# CAN.net
KiCad netlist of a schematic drawn in Altium Designer
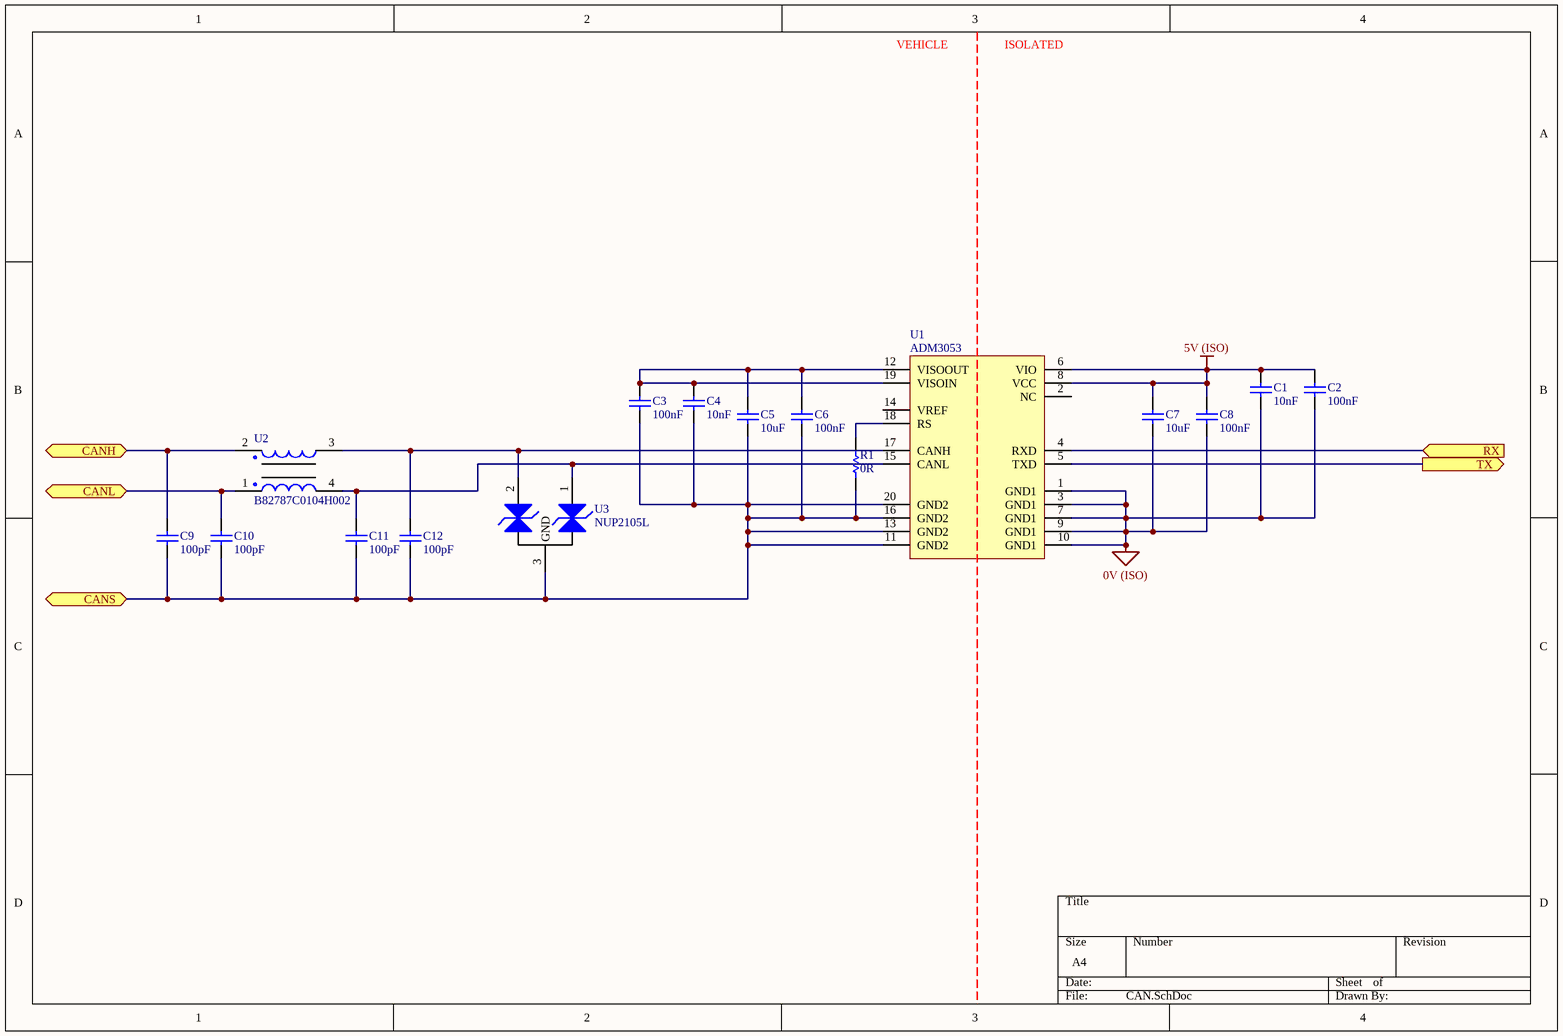
[diagram p0: CAN.SchDoc]

(export (version "E")
  (design (tool "Eeschema 10.0.6"))
  (components
    (comp (ref "C1")
      (value "10nF")
      (footprint "1206")
      (fields
        (field (name "PART NUMBER") "GCM3195C2A103JA16D")
        (field (name "TOLERANCE") "5%")
        (field (name "MANUFACTURER") "muRata")
      )
      (libsource (lib "ts_19-standard-library") (part "Capacitor"))
    )
    (comp (ref "C2")
      (value "100nF")
      (footprint "0805")
      (fields
        (field (name "PART NUMBER") "GCM21BR71E104KA37L")
        (field (name "TOLERANCE") "10%")
        (field (name "MANUFACTURER") "muRata")
      )
      (libsource (lib "ts_19-standard-library") (part "Capacitor"))
    )
    (comp (ref "C3")
      (value "100nF")
      (footprint "0805")
      (fields
        (field (name "PART NUMBER") "GCM21BR71E104KA37L")
        (field (name "TOLERANCE") "10%")
        (field (name "MANUFACTURER") "muRata")
      )
      (libsource (lib "ts_19-standard-library") (part "Capacitor"))
    )
    (comp (ref "C4")
      (value "10nF")
      (footprint "1206")
      (fields
        (field (name "PART NUMBER") "GCM3195C2A103JA16D")
        (field (name "TOLERANCE") "5%")
        (field (name "MANUFACTURER") "muRata")
      )
      (libsource (lib "ts_19-standard-library") (part "Capacitor"))
    )
    (comp (ref "C5")
      (value "10uF")
      (footprint "0805")
      (fields
        (field (name "PART NUMBER") "GRM21BR6YA106KE43L")
        (field (name "TOLERANCE") "10%")
        (field (name "MANUFACTURER") "muRata")
      )
      (libsource (lib "ts_19-standard-library") (part "Capacitor"))
    )
    (comp (ref "C6")
      (value "100nF")
      (footprint "0805")
      (fields
        (field (name "PART NUMBER") "GCM21BR71E104KA37L")
        (field (name "TOLERANCE") "10%")
        (field (name "MANUFACTURER") "muRata")
      )
      (libsource (lib "ts_19-standard-library") (part "Capacitor"))
    )
    (comp (ref "C7")
      (value "10uF")
      (footprint "0805")
      (fields
        (field (name "PART NUMBER") "GRM21BR6YA106KE43L")
        (field (name "TOLERANCE") "10%")
        (field (name "MANUFACTURER") "muRata")
      )
      (libsource (lib "ts_19-standard-library") (part "Capacitor"))
    )
    (comp (ref "C8")
      (value "100nF")
      (footprint "0805")
      (fields
        (field (name "PART NUMBER") "GCM21BR71E104KA37L")
        (field (name "TOLERANCE") "10%")
        (field (name "MANUFACTURER") "muRata")
      )
      (libsource (lib "ts_19-standard-library") (part "Capacitor"))
    )
    (comp (ref "C9")
      (value "100pF")
      (footprint "0805")
      (fields
        (field (name "PART NUMBER") "GCM21B5C1H101JA37L")
        (field (name "TOLERANCE") "5%")
        (field (name "MANUFACTURER") "muRata")
      )
      (libsource (lib "ts_19-standard-library") (part "Capacitor"))
    )
    (comp (ref "C10")
      (value "100pF")
      (footprint "0805")
      (fields
        (field (name "PART NUMBER") "GCM21B5C1H101JA37L")
        (field (name "TOLERANCE") "5%")
        (field (name "MANUFACTURER") "muRata")
      )
      (libsource (lib "ts_19-standard-library") (part "Capacitor"))
    )
    (comp (ref "C11")
      (value "100pF")
      (footprint "0805")
      (fields
        (field (name "PART NUMBER") "GCM21B5C1H101JA37L")
        (field (name "TOLERANCE") "5%")
        (field (name "MANUFACTURER") "muRata")
      )
      (libsource (lib "ts_19-standard-library") (part "Capacitor"))
    )
    (comp (ref "C12")
      (value "100pF")
      (footprint "0805")
      (fields
        (field (name "PART NUMBER") "GCM21B5C1H101JA37L")
        (field (name "TOLERANCE") "5%")
        (field (name "MANUFACTURER") "muRata")
      )
      (libsource (lib "ts_19-standard-library") (part "Capacitor"))
    )
    (comp (ref "R1")
      (value "0R")
      (footprint "0805")
      (fields
        (field (name "TOLERANCE") "0.01")
        (field (name "PART NUMBER") "RC0805FR070RL")
        (field (name "MANUFACTURER") "YAGEO")
      )
      (libsource (lib "ts_19-standard-library") (part "Resistor"))
    )
    (comp (ref "U1")
      (value "ADM3053")
      (footprint "AD SOIC-W 20")
      (description "Isolated CAN Transceiver")
      (fields
        (field (name "MANUFACTURER") "Analogue Devices")
        (field (name "DIGIKEY PART NUMBER") "ADM3053BRWZ-ND")
      )
      (libsource (lib "ts_19-standard-library") (part "ADM3053"))
    )
    (comp (ref "U2")
      (value "B82787C0104H002")
      (footprint "TDK 4-PC Pad")
      (description "Common mode choke intended for CANBUS 150mA 50V)")
      (fields
        (field (name "MANUFACTURER") "EPCOS (TDK)")
        (field (name "DIGIKEY PART NUMBER") "495-4598-2-ND")
      )
      (libsource (lib "ts_19-standard-library") (part "B82787C0104H002"))
    )
    (comp (ref "U3")
      (value "NUP2105L")
      (footprint "ON SOT-23")
      (description "Dual Line CAN Bus Protector")
      (fields
        (field (name "MANUFACTURER") "ON Semiconductor")
        (field (name "DIGIKEY PART NUMBER") "NUP2105LT1GOSCT-ND")
      )
      (libsource (lib "ts_19-standard-library") (part "NUP2105L"))
    )
  )
  (nets
    (net (code "1") (name "/CANH") (class "Default")
      (node (ref "C9") (pin "2") (pinfunction "2_2") (pintype "passive"))
      (node (ref "U2") (pin "2") (pinfunction "2_2") (pintype "passive"))
    )
    (net (code "2") (name "/CANL") (class "Default")
      (node (ref "C10") (pin "2") (pinfunction "2_2") (pintype "passive"))
      (node (ref "U2") (pin "1") (pinfunction "1_1") (pintype "passive"))
    )
    (net (code "3") (name "/CANS") (class "Default")
      (node (ref "C10") (pin "1") (pinfunction "1_1") (pintype "passive"))
      (node (ref "C11") (pin "1") (pinfunction "1_1") (pintype "passive"))
      (node (ref "C12") (pin "1") (pinfunction "1_1") (pintype "passive"))
      (node (ref "C3") (pin "1") (pinfunction "1_1") (pintype "passive"))
      (node (ref "C4") (pin "1") (pinfunction "1_1") (pintype "passive"))
      (node (ref "C5") (pin "1") (pinfunction "1_1") (pintype "passive"))
      (node (ref "C6") (pin "1") (pinfunction "1_1") (pintype "passive"))
      (node (ref "C9") (pin "1") (pinfunction "1_1") (pintype "passive"))
      (node (ref "R1") (pin "1") (pinfunction "1_1") (pintype "passive"))
      (node (ref "U1") (pin "11") (pinfunction "GND2_11") (pintype "passive"))
      (node (ref "U1") (pin "13") (pinfunction "GND2_13") (pintype "passive"))
      (node (ref "U1") (pin "16") (pinfunction "GND2_16") (pintype "passive"))
      (node (ref "U1") (pin "20") (pinfunction "GND2_20") (pintype "passive"))
      (node (ref "U3") (pin "3") (pinfunction "GND_3") (pintype "power_in"))
    )
    (net (code "4") (name "/RX") (class "Default")
      (node (ref "U1") (pin "4") (pinfunction "RXD_4") (pintype "passive"))
    )
    (net (code "5") (name "/TX") (class "Default")
      (node (ref "U1") (pin "5") (pinfunction "TXD_5") (pintype "passive"))
    )
    (net (code "6") (name "0V (ISO)") (class "Default")
      (node (ref "C1") (pin "1") (pinfunction "1_1") (pintype "passive"))
      (node (ref "C2") (pin "1") (pinfunction "1_1") (pintype "passive"))
      (node (ref "C7") (pin "1") (pinfunction "1_1") (pintype "passive"))
      (node (ref "C8") (pin "1") (pinfunction "1_1") (pintype "passive"))
      (node (ref "U1") (pin "1") (pinfunction "GND1_1") (pintype "passive"))
      (node (ref "U1") (pin "10") (pinfunction "GND1_10") (pintype "passive"))
      (node (ref "U1") (pin "3") (pinfunction "GND1_3") (pintype "passive"))
      (node (ref "U1") (pin "7") (pinfunction "GND1_7") (pintype "passive"))
      (node (ref "U1") (pin "9") (pinfunction "GND1_9") (pintype "passive"))
    )
    (net (code "7") (name "5V (ISO)") (class "Default")
      (node (ref "C1") (pin "2") (pinfunction "2_2") (pintype "passive"))
      (node (ref "C2") (pin "2") (pinfunction "2_2") (pintype "passive"))
      (node (ref "C7") (pin "2") (pinfunction "2_2") (pintype "passive"))
      (node (ref "C8") (pin "2") (pinfunction "2_2") (pintype "passive"))
      (node (ref "U1") (pin "6") (pinfunction "VIO_6") (pintype "passive"))
      (node (ref "U1") (pin "8") (pinfunction "VCC_8") (pintype "passive"))
    )
    (net (code "8") (name "Net-(U1-CANH)") (class "Default")
      (node (ref "C12") (pin "2") (pinfunction "2_2") (pintype "passive"))
      (node (ref "U1") (pin "17") (pinfunction "CANH_17") (pintype "passive"))
      (node (ref "U2") (pin "3") (pinfunction "3_3") (pintype "power_in"))
      (node (ref "U3") (pin "2") (pinfunction "CAN_L_2") (pintype "passive"))
    )
    (net (code "9") (name "Net-(U1-CANL)") (class "Default")
      (node (ref "C11") (pin "2") (pinfunction "2_2") (pintype "passive"))
      (node (ref "U1") (pin "15") (pinfunction "CANL_15") (pintype "passive"))
      (node (ref "U2") (pin "4") (pinfunction "4_4") (pintype "passive"))
      (node (ref "U3") (pin "1") (pinfunction "CAN_H_1") (pintype "passive"))
    )
    (net (code "10") (name "Net-(U1-RS)") (class "Default")
      (node (ref "R1") (pin "2") (pinfunction "2_2") (pintype "passive"))
      (node (ref "U1") (pin "18") (pinfunction "RS_18") (pintype "passive"))
    )
    (net (code "11") (name "Net-(U1-VISOIN)") (class "Default")
      (node (ref "C3") (pin "2") (pinfunction "2_2") (pintype "passive"))
      (node (ref "C4") (pin "2") (pinfunction "2_2") (pintype "passive"))
      (node (ref "C5") (pin "2") (pinfunction "2_2") (pintype "passive"))
      (node (ref "C6") (pin "2") (pinfunction "2_2") (pintype "passive"))
      (node (ref "U1") (pin "12") (pinfunction "VISOOUT_12") (pintype "passive"))
      (node (ref "U1") (pin "19") (pinfunction "VISOIN_19") (pintype "passive"))
    )
    (net (code "12") (name "unconnected-(U1-NC-Pad2)") (class "Default")
      (node (ref "U1") (pin "2") (pinfunction "NC_2") (pintype "passive"))
    )
    (net (code "13") (name "unconnected-(U1-VREF-Pad14)") (class "Default")
      (node (ref "U1") (pin "14") (pinfunction "VREF_14") (pintype "passive"))
    )
  )
)
